# ethernet_dual_100mbe_ext_magn.net
KiCad netlist of a schematic drawn in Altium Designer
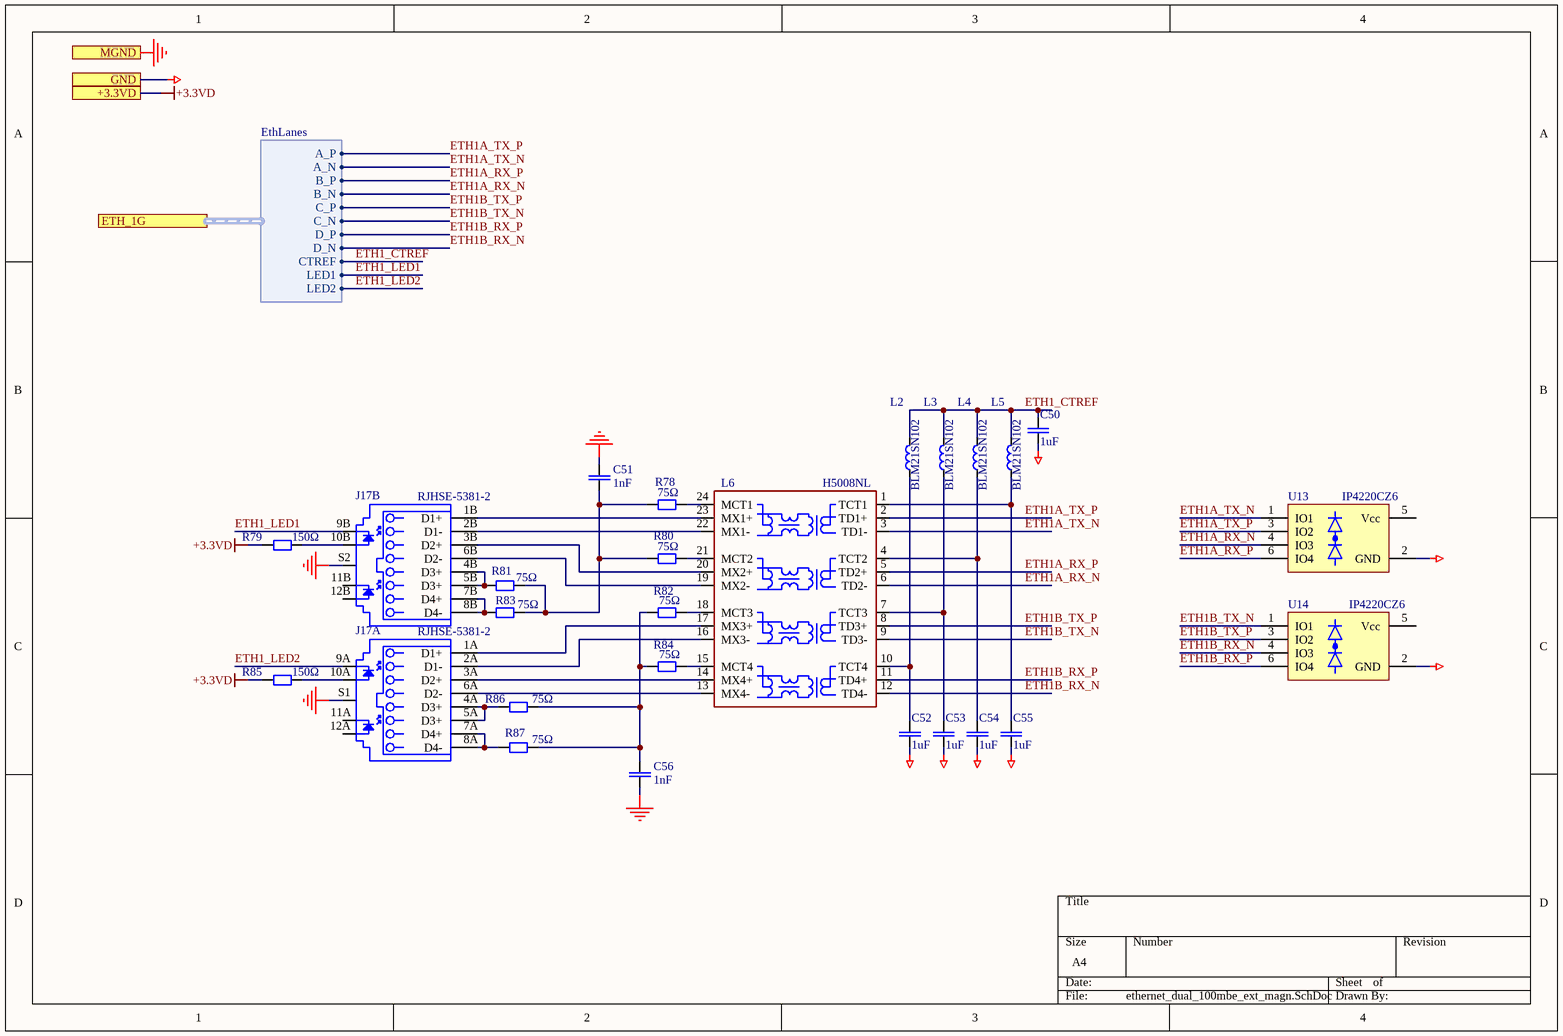
[diagram p0: ethernet_dual_100mbe_ext_magn.SchDoc]

(export (version "E")
  (design (tool "Eeschema 10.0.6"))
  (components
    (comp (ref "C50")
      (value "1uF")
      (footprint "CAPC2012N")
      (description "Generic ceramic SMD capacitor")
      (fields (field (name "MAINTAINER") "Evgeniy Kotov"))
      (libsource (lib "[Capacitors] Capacitors SMD") (part "CAPC"))
    )
    (comp (ref "C51")
      (value "1nF")
      (footprint "CAPC3216N")
      (description "Generic ceramic SMD capacitor")
      (fields (field (name "Comment") "1nF; 2kV") (field (name "MAINTAINER") "Evgeniy Kotov"))
      (libsource (lib "[Capacitors] Capacitors SMD") (part "CAPC"))
    )
    (comp (ref "C52")
      (value "1uF")
      (footprint "CAPC2012N")
      (description "Generic ceramic SMD capacitor")
      (fields (field (name "MAINTAINER") "Evgeniy Kotov"))
      (libsource (lib "[Capacitors] Capacitors SMD") (part "CAPC"))
    )
    (comp (ref "C53")
      (value "1uF")
      (footprint "CAPC2012N")
      (description "Generic ceramic SMD capacitor")
      (fields (field (name "MAINTAINER") "Evgeniy Kotov"))
      (libsource (lib "[Capacitors] Capacitors SMD") (part "CAPC"))
    )
    (comp (ref "C54")
      (value "1uF")
      (footprint "CAPC2012N")
      (description "Generic ceramic SMD capacitor")
      (fields (field (name "MAINTAINER") "Evgeniy Kotov"))
      (libsource (lib "[Capacitors] Capacitors SMD") (part "CAPC"))
    )
    (comp (ref "C55")
      (value "1uF")
      (footprint "CAPC2012N")
      (description "Generic ceramic SMD capacitor")
      (fields (field (name "MAINTAINER") "Evgeniy Kotov"))
      (libsource (lib "[Capacitors] Capacitors SMD") (part "CAPC"))
    )
    (comp (ref "C56")
      (value "1nF")
      (footprint "CAPC3216N")
      (description "Generic ceramic SMD capacitor")
      (fields (field (name "Comment") "1nF; 2kV") (field (name "MAINTAINER") "Evgeniy Kotov"))
      (libsource (lib "[Capacitors] Capacitors SMD") (part "CAPC"))
    )
    (comp (ref "J17")
      (value "RJHSE-5381-2")
      (footprint "AMPH-RJHSE-5381-02_V")
      (fields (field (name "MANUFACTURER") "Amphenol"))
      (libsource (lib "[Connectors] Miscellaneous") (part "RJ45-RJHSE-5381-2"))
    )
    (comp (ref "L2")
      (value "BLM21SN102")
      (footprint "INDC2012N")
      (description "Ferrite Beads, 0805, 1 kOhm")
      (fields
        (field (name "TOLERANCE") "25%")
        (field (name "Comment") "BLM21RK102SN1D")
        (field (name "MAINTAINER") "Evgeniy Kotov")
      )
      (libsource (lib "[Inductors & Transformers] Inductors SMD") (part "BLM21RK102SN1D"))
    )
    (comp (ref "L3")
      (value "BLM21SN102")
      (footprint "INDC2012N")
      (description "Ferrite Beads, 0805, 1 kOhm")
      (fields
        (field (name "TOLERANCE") "25%")
        (field (name "Comment") "BLM21RK102SN1D")
        (field (name "MAINTAINER") "Evgeniy Kotov")
      )
      (libsource (lib "[Inductors & Transformers] Inductors SMD") (part "BLM21RK102SN1D"))
    )
    (comp (ref "L4")
      (value "BLM21SN102")
      (footprint "INDC2012N")
      (description "Ferrite Beads, 0805, 1 kOhm")
      (fields
        (field (name "TOLERANCE") "25%")
        (field (name "Comment") "BLM21RK102SN1D")
        (field (name "MAINTAINER") "Evgeniy Kotov")
      )
      (libsource (lib "[Inductors & Transformers] Inductors SMD") (part "BLM21RK102SN1D"))
    )
    (comp (ref "L5")
      (value "BLM21SN102")
      (footprint "INDC2012N")
      (description "Ferrite Beads, 0805, 1 kOhm")
      (fields
        (field (name "TOLERANCE") "25%")
        (field (name "Comment") "BLM21RK102SN1D")
        (field (name "MAINTAINER") "Evgeniy Kotov")
      )
      (libsource (lib "[Inductors & Transformers] Inductors SMD") (part "BLM21RK102SN1D"))
    )
    (comp (ref "L6")
      (value "H5008NL")
      (footprint "SMD_HX508")
      (description "LAN Transformer fog 1GbE, 12 coils, 4 pairs.")
      (fields (field (name "TOLERANCE") "2%") (field (name "MAINTAINER") "Evgeniy Kotov"))
      (libsource (lib "[Inductors & Transformers] Inductors SMD") (part "LAN_1G_TR_H5008NL"))
    )
    (comp (ref "R78")
      (value "75Ω")
      (footprint "RESC2012N")
      (description "Resistor, Generic, SMD")
      (fields (field (name "MAINTAINER") "Evgeniy Kotov"))
      (libsource (lib "[Resistors] Resistors SMD") (part "RESC"))
    )
    (comp (ref "R79")
      (value "150Ω")
      (footprint "RESC2012N")
      (description "Resistor, Generic, SMD")
      (fields (field (name "MAINTAINER") "Evgeniy Kotov"))
      (libsource (lib "[Resistors] Resistors SMD") (part "RESC"))
    )
    (comp (ref "R80")
      (value "75Ω")
      (footprint "RESC2012N")
      (description "Resistor, Generic, SMD")
      (fields (field (name "MAINTAINER") "Evgeniy Kotov"))
      (libsource (lib "[Resistors] Resistors SMD") (part "RESC"))
    )
    (comp (ref "R81")
      (value "75Ω")
      (footprint "RESC2012N")
      (description "Resistor, Generic, SMD")
      (fields (field (name "MAINTAINER") "Evgeniy Kotov"))
      (libsource (lib "[Resistors] Resistors SMD") (part "RESC"))
    )
    (comp (ref "R82")
      (value "75Ω")
      (footprint "RESC2012N")
      (description "Resistor, Generic, SMD")
      (fields (field (name "MAINTAINER") "Evgeniy Kotov"))
      (libsource (lib "[Resistors] Resistors SMD") (part "RESC"))
    )
    (comp (ref "R83")
      (value "75Ω")
      (footprint "RESC2012N")
      (description "Resistor, Generic, SMD")
      (fields (field (name "MAINTAINER") "Evgeniy Kotov"))
      (libsource (lib "[Resistors] Resistors SMD") (part "RESC"))
    )
    (comp (ref "R84")
      (value "75Ω")
      (footprint "RESC2012N")
      (description "Resistor, Generic, SMD")
      (fields (field (name "MAINTAINER") "Evgeniy Kotov"))
      (libsource (lib "[Resistors] Resistors SMD") (part "RESC"))
    )
    (comp (ref "R85")
      (value "150Ω")
      (footprint "RESC2012N")
      (description "Resistor, Generic, SMD")
      (fields (field (name "MAINTAINER") "Evgeniy Kotov"))
      (libsource (lib "[Resistors] Resistors SMD") (part "RESC"))
    )
    (comp (ref "R86")
      (value "75Ω")
      (footprint "RESC2012N")
      (description "Resistor, Generic, SMD")
      (fields (field (name "MAINTAINER") "Evgeniy Kotov"))
      (libsource (lib "[Resistors] Resistors SMD") (part "RESC"))
    )
    (comp (ref "R87")
      (value "75Ω")
      (footprint "RESC2012N")
      (description "Resistor, Generic, SMD")
      (fields (field (name "MAINTAINER") "Evgeniy Kotov"))
      (libsource (lib "[Resistors] Resistors SMD") (part "RESC"))
    )
    (comp (ref "U13")
      (value "IP4220CZ6")
      (footprint "SOT95P285X110-6N")
      (description "Transimpedance Amplifier; Selectable-Feedback Resistance")
      (fields (field (name "MAINTAINER") "Evgeniy Kotov"))
      (libsource (lib "[ICs And Semiconductors] Diodes") (part "IP4220CZ6"))
    )
    (comp (ref "U14")
      (value "IP4220CZ6")
      (footprint "SOT95P285X110-6N")
      (description "Transimpedance Amplifier; Selectable-Feedback Resistance")
      (fields (field (name "MAINTAINER") "Evgeniy Kotov"))
      (libsource (lib "[ICs And Semiconductors] Diodes") (part "IP4220CZ6"))
    )
  )
  (nets
    (net (code "2") (name "+3.3VD") (class "Default")
      (node (ref "R79") (pin "1") (pintype "passive"))
      (node (ref "R85") (pin "1") (pintype "passive"))
    )
    (net (code "3") (name "/ETH1A_RX_N") (class "Default")
      (node (ref "L6") (pin "6") (pinfunction "TD2-_6") (pintype "passive"))
      (node (ref "U13") (pin "4") (pinfunction "IO3_4") (pintype "passive"))
    )
    (net (code "4") (name "/ETH1A_RX_P") (class "Default")
      (node (ref "L6") (pin "5") (pinfunction "TD2+_5") (pintype "passive"))
      (node (ref "U13") (pin "6") (pinfunction "IO4_6") (pintype "passive"))
    )
    (net (code "5") (name "/ETH1A_TX_N") (class "Default")
      (node (ref "L6") (pin "3") (pinfunction "TD1-_3") (pintype "passive"))
      (node (ref "U13") (pin "1") (pinfunction "IO1_1") (pintype "passive"))
    )
    (net (code "6") (name "/ETH1A_TX_P") (class "Default")
      (node (ref "L6") (pin "2") (pinfunction "TD1+_2") (pintype "passive"))
      (node (ref "U13") (pin "3") (pinfunction "IO2_3") (pintype "passive"))
    )
    (net (code "7") (name "/ETH1B_RX_N") (class "Default")
      (node (ref "L6") (pin "12") (pinfunction "TD4-_12") (pintype "passive"))
      (node (ref "U14") (pin "4") (pinfunction "IO3_4") (pintype "passive"))
    )
    (net (code "8") (name "/ETH1B_RX_P") (class "Default")
      (node (ref "L6") (pin "11") (pinfunction "TD4+_11") (pintype "passive"))
      (node (ref "U14") (pin "6") (pinfunction "IO4_6") (pintype "passive"))
    )
    (net (code "9") (name "/ETH1B_TX_N") (class "Default")
      (node (ref "L6") (pin "9") (pinfunction "TD3-_9") (pintype "passive"))
      (node (ref "U14") (pin "1") (pinfunction "IO1_1") (pintype "passive"))
    )
    (net (code "10") (name "/ETH1B_TX_P") (class "Default")
      (node (ref "L6") (pin "8") (pinfunction "TD3+_8") (pintype "passive"))
      (node (ref "U14") (pin "3") (pinfunction "IO2_3") (pintype "passive"))
    )
    (net (code "11") (name "/ETH1_CTREF") (class "Default")
      (node (ref "C50") (pin "2") (pintype "passive"))
      (node (ref "L2") (pin "2") (pinfunction "2_2") (pintype "passive"))
      (node (ref "L3") (pin "2") (pinfunction "2_2") (pintype "passive"))
      (node (ref "L4") (pin "2") (pinfunction "2_2") (pintype "passive"))
      (node (ref "L5") (pin "2") (pinfunction "2_2") (pintype "passive"))
    )
    (net (code "12") (name "/ETH1_LED1") (class "Default")
      (node (ref "J17") (pin "9B") (pinfunction "9_9B") (pintype "passive"))
    )
    (net (code "13") (name "/ETH1_LED2") (class "Default")
      (node (ref "J17") (pin "9A") (pinfunction "9_9A") (pintype "passive"))
    )
    (net (code "15") (name "GND") (class "Default")
      (node (ref "C50") (pin "1") (pintype "passive"))
      (node (ref "C52") (pin "1") (pintype "passive"))
      (node (ref "C53") (pin "1") (pintype "passive"))
      (node (ref "C54") (pin "1") (pintype "passive"))
      (node (ref "C55") (pin "1") (pintype "passive"))
      (node (ref "U13") (pin "2") (pinfunction "GND_2") (pintype "passive"))
      (node (ref "U14") (pin "2") (pinfunction "GND_2") (pintype "passive"))
    )
    (net (code "16") (name "MGND") (class "Default")
      (node (ref "C51") (pin "2") (pintype "passive"))
      (node (ref "C56") (pin "1") (pintype "passive"))
      (node (ref "J17") (pin "S1") (pinfunction "S1_S1") (pintype "passive"))
      (node (ref "J17") (pin "S2") (pinfunction "S2_S2") (pintype "passive"))
    )
    (net (code "17") (name "Net-(C51-Pad1)") (class "Default")
      (node (ref "C51") (pin "1") (pintype "passive"))
      (node (ref "R78") (pin "1") (pintype "passive"))
      (node (ref "R80") (pin "1") (pintype "passive"))
      (node (ref "R81") (pin "2") (pintype "passive"))
      (node (ref "R83") (pin "2") (pintype "passive"))
    )
    (net (code "18") (name "Net-(C56-Pad2)") (class "Default")
      (node (ref "C56") (pin "2") (pintype "passive"))
      (node (ref "R82") (pin "1") (pintype "passive"))
      (node (ref "R84") (pin "1") (pintype "passive"))
      (node (ref "R86") (pin "2") (pintype "passive"))
      (node (ref "R87") (pin "2") (pintype "passive"))
    )
    (net (code "19") (name "Net-(J17A-10)") (class "Default")
      (node (ref "J17") (pin "10A") (pinfunction "10_10A") (pintype "passive"))
      (node (ref "R85") (pin "2") (pintype "passive"))
    )
    (net (code "20") (name "Net-(J17A-D1+)") (class "Default")
      (node (ref "J17") (pin "1A") (pinfunction "D1+_1A") (pintype "passive"))
      (node (ref "L6") (pin "17") (pinfunction "MX3+_17") (pintype "passive"))
    )
    (net (code "21") (name "Net-(J17A-D1-)") (class "Default")
      (node (ref "J17") (pin "2A") (pinfunction "D1-_2A") (pintype "passive"))
      (node (ref "L6") (pin "16") (pinfunction "MX3-_16") (pintype "passive"))
    )
    (net (code "22") (name "Net-(J17A-D2+)") (class "Default")
      (node (ref "J17") (pin "3A") (pinfunction "D2+_3A") (pintype "passive"))
      (node (ref "L6") (pin "14") (pinfunction "MX4+_14") (pintype "passive"))
    )
    (net (code "23") (name "Net-(J17A-D2-)") (class "Default")
      (node (ref "J17") (pin "6A") (pinfunction "D2-_6A") (pintype "passive"))
      (node (ref "L6") (pin "13") (pinfunction "MX4-_13") (pintype "passive"))
    )
    (net (code "24") (name "Net-(J17A-D3+-Pad4A)") (class "Default")
      (node (ref "J17") (pin "4A") (pinfunction "D3+_4A") (pintype "passive"))
      (node (ref "J17") (pin "5A") (pinfunction "D3+_5A") (pintype "passive"))
      (node (ref "R86") (pin "1") (pintype "passive"))
    )
    (net (code "25") (name "Net-(J17A-D4+)") (class "Default")
      (node (ref "J17") (pin "7A") (pinfunction "D4+_7A") (pintype "passive"))
      (node (ref "J17") (pin "8A") (pinfunction "D4-_8A") (pintype "passive"))
      (node (ref "R87") (pin "1") (pintype "passive"))
    )
    (net (code "26") (name "Net-(J17B-10)") (class "Default")
      (node (ref "J17") (pin "10B") (pinfunction "10_10B") (pintype "passive"))
      (node (ref "R79") (pin "2") (pintype "passive"))
    )
    (net (code "27") (name "Net-(J17B-D1+)") (class "Default")
      (node (ref "J17") (pin "1B") (pinfunction "D1+_1B") (pintype "passive"))
      (node (ref "L6") (pin "23") (pinfunction "MX1+_23") (pintype "passive"))
    )
    (net (code "28") (name "Net-(J17B-D1-)") (class "Default")
      (node (ref "J17") (pin "2B") (pinfunction "D1-_2B") (pintype "passive"))
      (node (ref "L6") (pin "22") (pinfunction "MX1-_22") (pintype "passive"))
    )
    (net (code "29") (name "Net-(J17B-D2+)") (class "Default")
      (node (ref "J17") (pin "3B") (pinfunction "D2+_3B") (pintype "passive"))
      (node (ref "L6") (pin "20") (pinfunction "MX2+_20") (pintype "passive"))
    )
    (net (code "30") (name "Net-(J17B-D2-)") (class "Default")
      (node (ref "J17") (pin "6B") (pinfunction "D2-_6B") (pintype "passive"))
      (node (ref "L6") (pin "19") (pinfunction "MX2-_19") (pintype "passive"))
    )
    (net (code "31") (name "Net-(J17B-D3+-Pad4B)") (class "Default")
      (node (ref "J17") (pin "4B") (pinfunction "D3+_4B") (pintype "passive"))
      (node (ref "J17") (pin "5B") (pinfunction "D3+_5B") (pintype "passive"))
      (node (ref "R81") (pin "1") (pintype "passive"))
    )
    (net (code "32") (name "Net-(J17B-D4+)") (class "Default")
      (node (ref "J17") (pin "7B") (pinfunction "D4+_7B") (pintype "passive"))
      (node (ref "J17") (pin "8B") (pinfunction "D4-_8B") (pintype "passive"))
      (node (ref "R83") (pin "1") (pintype "passive"))
    )
    (net (code "33") (name "Net-(L6-MCT1)") (class "Default")
      (node (ref "L6") (pin "24") (pinfunction "MCT1_24") (pintype "passive"))
      (node (ref "R78") (pin "2") (pintype "passive"))
    )
    (net (code "34") (name "Net-(L6-MCT2)") (class "Default")
      (node (ref "L6") (pin "21") (pinfunction "MCT2_21") (pintype "passive"))
      (node (ref "R80") (pin "2") (pintype "passive"))
    )
    (net (code "35") (name "Net-(L6-MCT3)") (class "Default")
      (node (ref "L6") (pin "18") (pinfunction "MCT3_18") (pintype "passive"))
      (node (ref "R82") (pin "2") (pintype "passive"))
    )
    (net (code "36") (name "Net-(L6-MCT4)") (class "Default")
      (node (ref "L6") (pin "15") (pinfunction "MCT4_15") (pintype "passive"))
      (node (ref "R84") (pin "2") (pintype "passive"))
    )
    (net (code "37") (name "Net-(L6-TCT1)") (class "Default")
      (node (ref "C55") (pin "2") (pintype "passive"))
      (node (ref "L5") (pin "1") (pinfunction "1_1") (pintype "passive"))
      (node (ref "L6") (pin "1") (pinfunction "TCT1_1") (pintype "passive"))
    )
    (net (code "38") (name "Net-(L6-TCT2)") (class "Default")
      (node (ref "C54") (pin "2") (pintype "passive"))
      (node (ref "L4") (pin "1") (pinfunction "1_1") (pintype "passive"))
      (node (ref "L6") (pin "4") (pinfunction "TCT2_4") (pintype "passive"))
    )
    (net (code "39") (name "Net-(L6-TCT3)") (class "Default")
      (node (ref "C53") (pin "2") (pintype "passive"))
      (node (ref "L3") (pin "1") (pinfunction "1_1") (pintype "passive"))
      (node (ref "L6") (pin "7") (pinfunction "TCT3_7") (pintype "passive"))
    )
    (net (code "40") (name "Net-(L6-TCT4)") (class "Default")
      (node (ref "C52") (pin "2") (pintype "passive"))
      (node (ref "L2") (pin "1") (pinfunction "1_1") (pintype "passive"))
      (node (ref "L6") (pin "10") (pinfunction "TCT4_10") (pintype "passive"))
    )
    (net (code "41") (name "unconnected-(J17A-11-Pad11A)") (class "Default")
      (node (ref "J17") (pin "11A") (pinfunction "11_11A") (pintype "passive"))
    )
    (net (code "42") (name "unconnected-(J17A-12-Pad12A)") (class "Default")
      (node (ref "J17") (pin "12A") (pinfunction "12_12A") (pintype "passive"))
    )
    (net (code "43") (name "unconnected-(J17B-11-Pad11B)") (class "Default")
      (node (ref "J17") (pin "11B") (pinfunction "11_11B") (pintype "passive"))
    )
    (net (code "44") (name "unconnected-(J17B-12-Pad12B)") (class "Default")
      (node (ref "J17") (pin "12B") (pinfunction "12_12B") (pintype "passive"))
    )
    (net (code "45") (name "unconnected-(U13-Vcc-Pad5)") (class "Default")
      (node (ref "U13") (pin "5") (pinfunction "Vcc_5") (pintype "passive"))
    )
    (net (code "46") (name "unconnected-(U14-Vcc-Pad5)") (class "Default")
      (node (ref "U14") (pin "5") (pinfunction "Vcc_5") (pintype "passive"))
    )
  )
)
